# design.net
KiCad netlist of a schematic drawn in Altium Designer
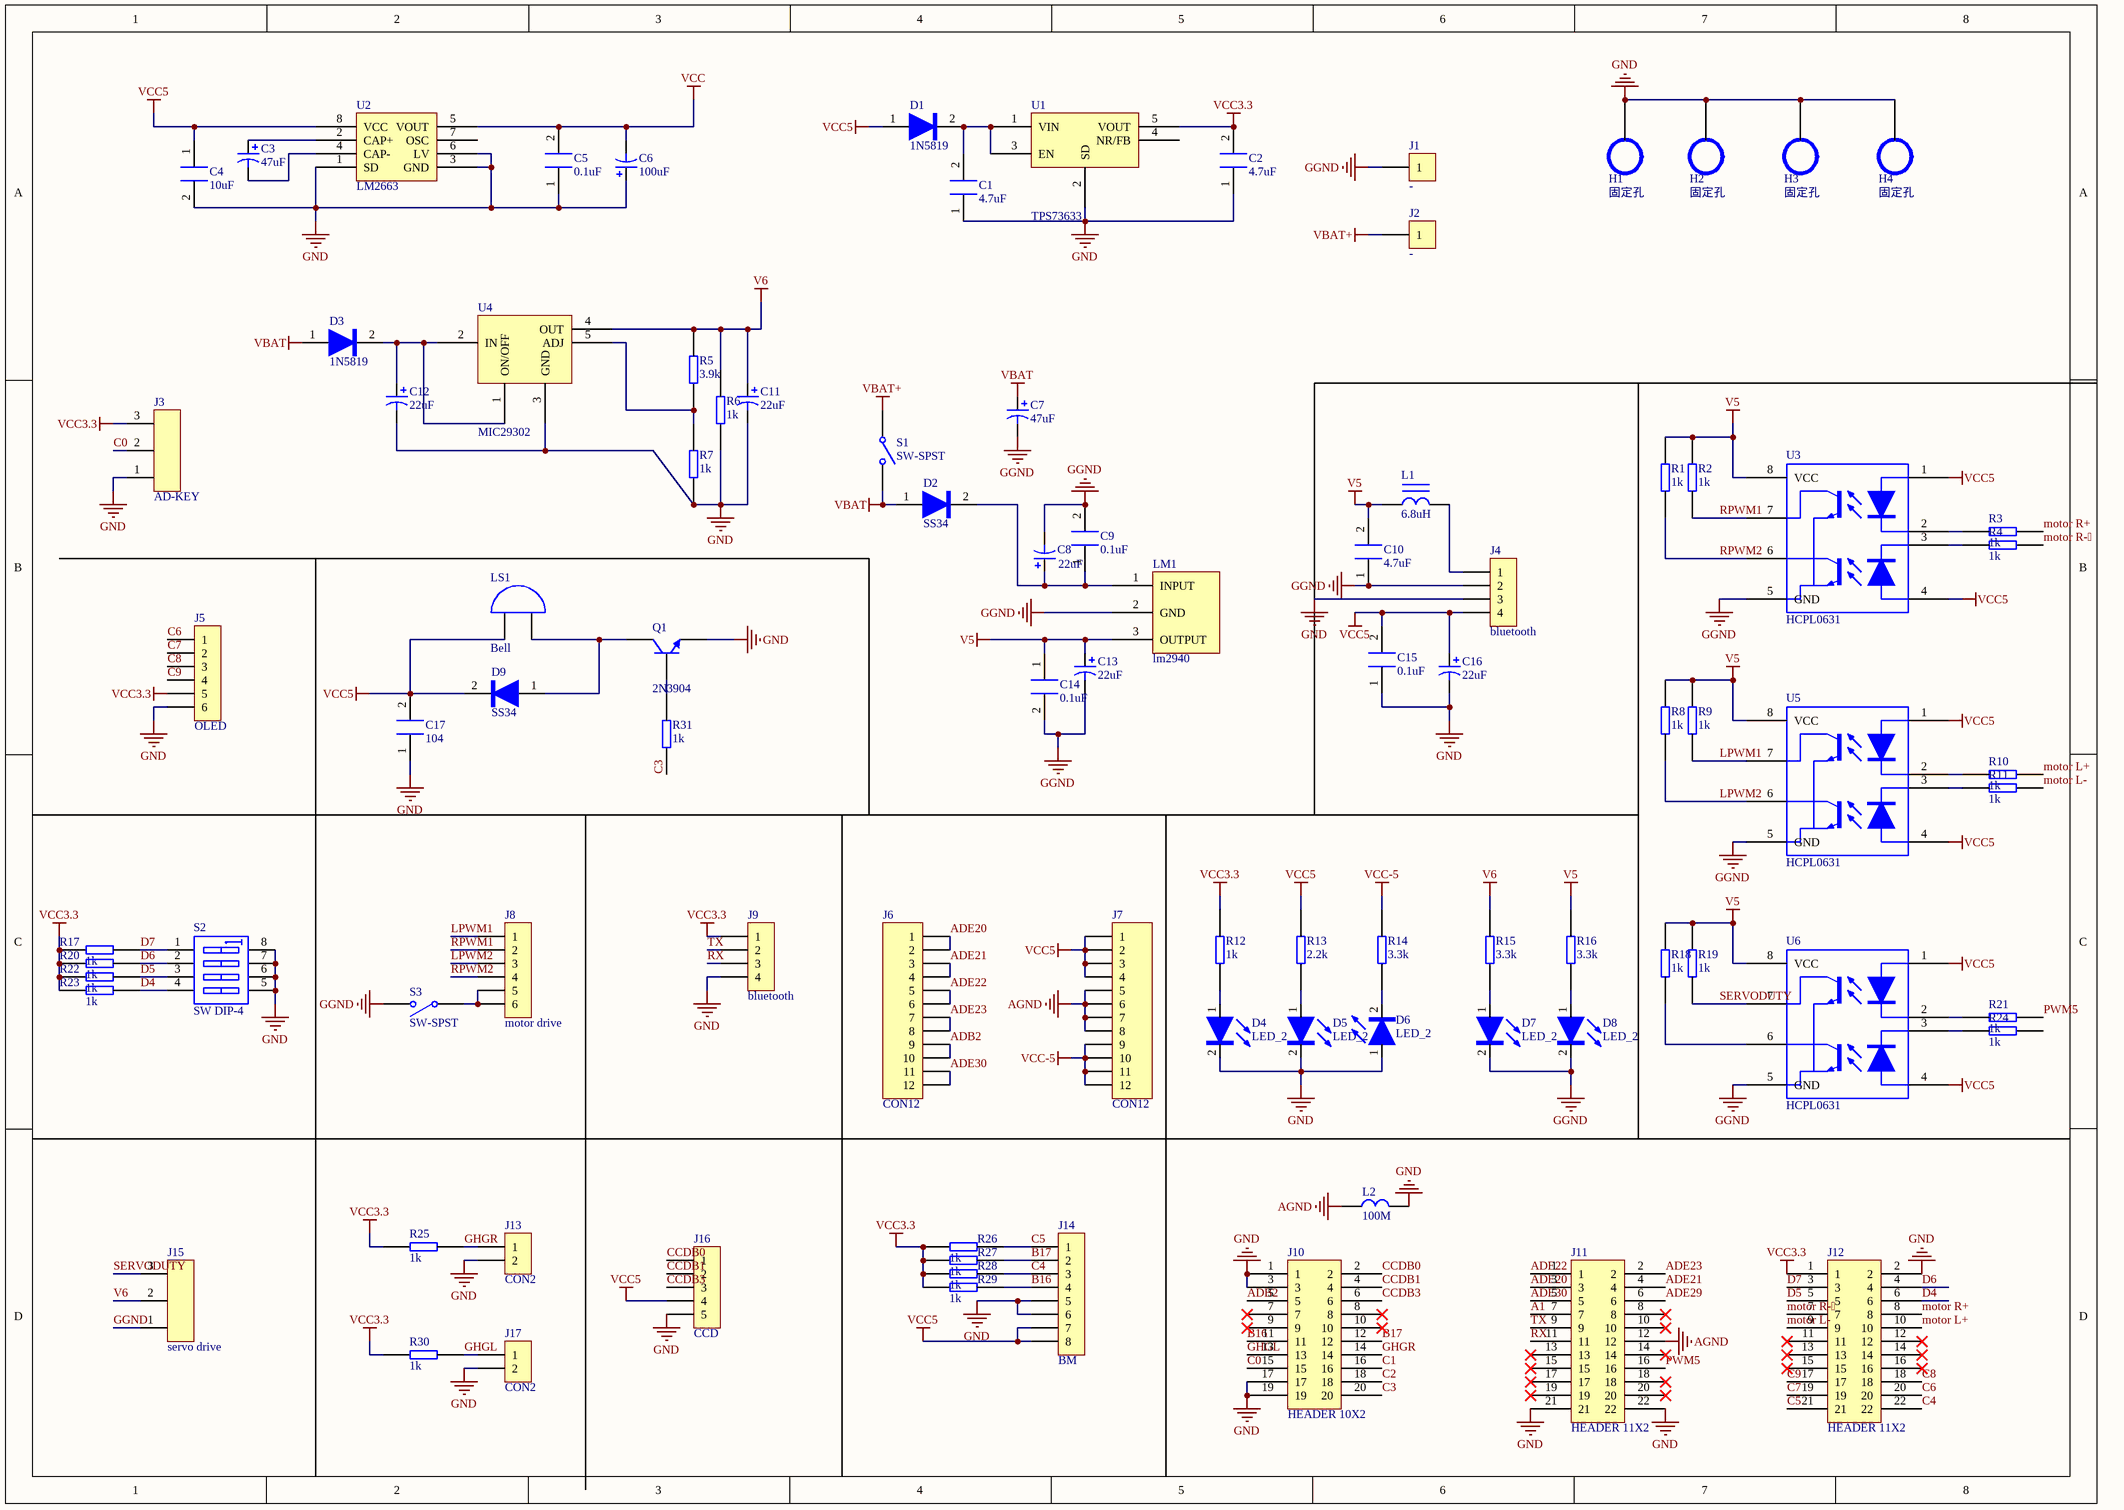
[diagram p0: 智能小车主板.SchDoc]

(export (version "E")
  (design (tool "Eeschema 10.0.6"))
  (components
    (comp (ref "C1")
      (value "4.7uF")
      (footprint "0805C")
      (description "电容")
      (libsource (lib "智能车主板") (part "CAP_2"))
    )
    (comp (ref "C2")
      (value "4.7uF")
      (footprint "0805C")
      (description "电容")
      (libsource (lib "智能车主板") (part "CAP_2"))
    )
    (comp (ref "C3")
      (value "47uF")
      (footprint "C型钽电容_6032_28")
      (description "极性电容")
      (libsource (lib "智能车主板") (part "极性电容"))
    )
    (comp (ref "C4")
      (value "10uF")
      (footprint "0805C")
      (description "电容")
      (libsource (lib "智能车主板") (part "CAP"))
    )
    (comp (ref "C5")
      (value "0.1uF")
      (footprint "0805C")
      (description "电容")
      (libsource (lib "智能车主板") (part "CAP_1"))
    )
    (comp (ref "C6")
      (value "100uF")
      (footprint "D型钽电容_7343_31")
      (description "极性电容")
      (libsource (lib "智能车主板") (part "极性电容_1"))
    )
    (comp (ref "C7")
      (value "47uF")
      (footprint "D型钽电容_7343_31")
      (description "极性电容")
      (libsource (lib "智能车主板") (part "极性电容"))
    )
    (comp (ref "C8")
      (value "22uF")
      (footprint "C型钽电容_6032_28")
      (description "极性电容")
      (libsource (lib "智能车主板") (part "极性电容_2"))
    )
    (comp (ref "C9")
      (value "0.1uF")
      (footprint "0805C")
      (description "电容")
      (libsource (lib "智能车主板") (part "CAP_1"))
    )
    (comp (ref "C10")
      (value "4.7uF")
      (footprint "0805C")
      (description "电容")
      (libsource (lib "智能车主板") (part "CAP_2"))
    )
    (comp (ref "C11")
      (value "22uF")
      (footprint "B型钽电容_3528_21")
      (description "极性电容")
      (libsource (lib "智能车主板") (part "极性电容_2"))
    )
    (comp (ref "C12")
      (value "22uF")
      (footprint "B型钽电容_3528_21")
      (description "极性电容")
      (libsource (lib "智能车主板") (part "极性电容_2"))
    )
    (comp (ref "C13")
      (value "22uF")
      (footprint "B型钽电容_3528_21")
      (description "极性电容")
      (libsource (lib "智能车主板") (part "极性电容_2"))
    )
    (comp (ref "C14")
      (value "0.1uF")
      (footprint "0805C")
      (description "电容")
      (libsource (lib "智能车主板") (part "CAP_1"))
    )
    (comp (ref "C15")
      (value "0.1uF")
      (footprint "0805C")
      (description "电容")
      (libsource (lib "智能车主板") (part "CAP_1"))
    )
    (comp (ref "C16")
      (value "22uF")
      (footprint "B型钽电容_3528_21")
      (description "极性电容")
      (libsource (lib "智能车主板") (part "极性电容_2"))
    )
    (comp (ref "C17")
      (value "104")
      (footprint "0805C")
      (description "电容")
      (libsource (lib "智能车主板") (part "CAP_3"))
    )
    (comp (ref "D1")
      (value "1N5819")
      (footprint "0805D")
      (description "二极管")
      (libsource (lib "智能车主板") (part "SS34"))
    )
    (comp (ref "D2")
      (value "SS34")
      (footprint "0805D")
      (description "二极管")
      (libsource (lib "智能车主板") (part "SS34_1"))
    )
    (comp (ref "D3")
      (value "1N5819")
      (footprint "0805D")
      (description "二极管")
      (libsource (lib "智能车主板") (part "SS34"))
    )
    (comp (ref "D4") (value "LED_2") (footprint "0805D") (libsource (lib "智能车主板") (part "LED")))
    (comp (ref "D5") (value "LED_2") (footprint "0805D") (libsource (lib "智能车主板") (part "LED")))
    (comp (ref "D6") (value "LED_2") (footprint "0805D") (libsource (lib "智能车主板") (part "LED")))
    (comp (ref "D7") (value "LED_2") (footprint "0805D") (libsource (lib "智能车主板") (part "LED")))
    (comp (ref "D8") (value "LED_2") (footprint "0805D") (libsource (lib "智能车主板") (part "LED")))
    (comp (ref "D9")
      (value "SS34")
      (footprint "SS34_3D")
      (description "二极管")
      (libsource (lib "智能车主板") (part "SS34_1"))
    )
    (comp (ref "H1") (value "固定孔") (footprint "铜柱孔3") (libsource (lib "智能车主板") (part "固定孔")))
    (comp (ref "H2") (value "固定孔") (footprint "铜柱孔3") (libsource (lib "智能车主板") (part "固定孔")))
    (comp (ref "H3") (value "固定孔") (footprint "铜柱孔3") (libsource (lib "智能车主板") (part "固定孔")))
    (comp (ref "H4") (value "固定孔") (footprint "铜柱孔3") (libsource (lib "智能车主板") (part "固定孔")))
    (comp (ref "J1")
      (value "-")
      (footprint "单面焊盘2*3MM_1PIN")
      (description "Connector")
      (libsource (lib "智能车主板") (part "CON1"))
    )
    (comp (ref "J2")
      (value "-")
      (footprint "单面焊盘2*3MM_1PIN")
      (description "Connector")
      (libsource (lib "智能车主板") (part "CON1"))
    )
    (comp (ref "J3")
      (value "AD-KEY")
      (footprint "HDR1X3")
      (description "SOCKET")
      (libsource (lib "智能车主板") (part "CON3"))
    )
    (comp (ref "J4")
      (value "bluetooth")
      (footprint "B0505S-2W")
      (description "Connector")
      (libsource (lib "智能车主板") (part "CON4"))
    )
    (comp (ref "J5")
      (value "OLED")
      (footprint "HDR1X6")
      (description "Connector")
      (libsource (lib "智能车主板") (part "CON6"))
    )
    (comp (ref "J6")
      (value "CON12")
      (footprint "HDR2X6")
      (description "Connector")
      (libsource (lib "") (part "CON12_1"))
    )
    (comp (ref "J7")
      (value "CON12")
      (footprint "HDR2X6")
      (description "Connector")
      (libsource (lib "智能车主板") (part "CON12"))
    )
    (comp (ref "J8")
      (value "motor drive")
      (footprint "HDR2X3")
      (description "Connector")
      (libsource (lib "智能车主板") (part "CON6_1"))
    )
    (comp (ref "J9")
      (value "bluetooth")
      (footprint "HDR1X4")
      (description "Connector")
      (libsource (lib "智能车主板") (part "CON4"))
    )
    (comp (ref "J10")
      (value "HEADER 10X2")
      (footprint "HDR2X10")
      (description "排针")
      (libsource (lib "智能车主板") (part "HEADER 10X2"))
    )
    (comp (ref "J11")
      (value "HEADER 11X2")
      (footprint "HDR2X11")
      (description "排针")
      (libsource (lib "智能车主板") (part "HEADER 11X2"))
    )
    (comp (ref "J12")
      (value "HEADER 11X2")
      (footprint "HDR2X11")
      (description "排针")
      (libsource (lib "智能车主板") (part "HEADER 11X2"))
    )
    (comp (ref "J13")
      (value "CON2")
      (footprint "2PIN杜邦插座_1.27mm")
      (description "Connector")
      (libsource (lib "智能车主板") (part "CON2"))
    )
    (comp (ref "J14")
      (value "BM")
      (footprint "HDR2X4")
      (description "Connector")
      (libsource (lib "智能车主板") (part "CON8"))
    )
    (comp (ref "J15")
      (value "servo drive")
      (footprint "HDR1X3")
      (description "SOCKET")
      (libsource (lib "智能车主板") (part "CON3_1"))
    )
    (comp (ref "J16")
      (value "CCD")
      (footprint "HDR1X5")
      (description "Connector")
      (libsource (lib "智能车主板") (part "CON5"))
    )
    (comp (ref "J17")
      (value "CON2")
      (footprint "2PIN杜邦插座_1.27mm")
      (description "Connector")
      (libsource (lib "智能车主板") (part "CON2"))
    )
    (comp (ref "L1")
      (value "6.8uH")
      (footprint "CDRH3D16_4.2*1.8")
      (description "电感")
      (libsource (lib "智能车主板") (part "INDUCTOR"))
    )
    (comp (ref "L2") (value "100M") (footprint "0603L") (libsource (lib "智能车主板") (part "INDUCTOR_2")))
    (comp (ref "LM1")
      (value "lm2940")
      (footprint "lm2940")
      (description "IC")
      (libsource (lib "智能车主板") (part "lm2940"))
    )
    (comp (ref "LS1")
      (value "Bell")
      (footprint "蜂鸣器侧装")
      (description "Electrical Bell")
      (fields (field (name "PUBLISHER") "Altium Limited"))
      (libsource (lib "智能车主板") (part "Bell"))
    )
    (comp (ref "Q1")
      (value "2N3904")
      (footprint "TO-92A")
      (description "NPN General Purpose Amplifier")
      (fields (field (name "PUBLISHER") "Altium Limited"))
      (libsource (lib "智能车主板") (part "2N3904"))
    )
    (comp (ref "R1")
      (value "1k")
      (footprint "0805R")
      (description "电阻")
      (libsource (lib "智能车主板") (part "RES_1"))
    )
    (comp (ref "R2")
      (value "1k")
      (footprint "0805R")
      (description "电阻")
      (libsource (lib "智能车主板") (part "RES_1"))
    )
    (comp (ref "R3")
      (value "1k")
      (footprint "0805R")
      (description "电阻")
      (libsource (lib "智能车主板") (part "RES_1"))
    )
    (comp (ref "R4")
      (value "1k")
      (footprint "0805R")
      (description "电阻")
      (libsource (lib "智能车主板") (part "RES_1"))
    )
    (comp (ref "R5")
      (value "3.9k")
      (footprint "0805R")
      (description "电阻")
      (libsource (lib "智能车主板") (part "RES"))
    )
    (comp (ref "R6")
      (value "1k")
      (footprint "0805R")
      (description "电阻")
      (libsource (lib "智能车主板") (part "RES_1"))
    )
    (comp (ref "R7")
      (value "1k")
      (footprint "0805R")
      (description "电阻")
      (libsource (lib "智能车主板") (part "RES_1"))
    )
    (comp (ref "R8")
      (value "1k")
      (footprint "0805R")
      (description "电阻")
      (libsource (lib "智能车主板") (part "RES_1"))
    )
    (comp (ref "R9")
      (value "1k")
      (footprint "0805R")
      (description "电阻")
      (libsource (lib "智能车主板") (part "RES_1"))
    )
    (comp (ref "R10")
      (value "1k")
      (footprint "0805R")
      (description "电阻")
      (libsource (lib "智能车主板") (part "RES_1"))
    )
    (comp (ref "R11")
      (value "1k")
      (footprint "0805R")
      (description "电阻")
      (libsource (lib "智能车主板") (part "RES_1"))
    )
    (comp (ref "R12")
      (value "1k")
      (footprint "0603R")
      (description "电阻")
      (libsource (lib "智能车主板") (part "RES_1"))
    )
    (comp (ref "R13")
      (value "2.2k")
      (footprint "0603R")
      (description "电阻")
      (libsource (lib "智能车主板") (part "RES_2"))
    )
    (comp (ref "R14")
      (value "3.3k")
      (footprint "0603R")
      (description "电阻")
      (libsource (lib "智能车主板") (part "RES_3"))
    )
    (comp (ref "R15")
      (value "3.3k")
      (footprint "0603R")
      (description "电阻")
      (libsource (lib "智能车主板") (part "RES_3"))
    )
    (comp (ref "R16")
      (value "3.3k")
      (footprint "0603R")
      (description "电阻")
      (libsource (lib "智能车主板") (part "RES_3"))
    )
    (comp (ref "R17")
      (value "1k")
      (footprint "0603R")
      (description "电阻")
      (libsource (lib "智能车主板") (part "RES_1"))
    )
    (comp (ref "R18")
      (value "1k")
      (footprint "0805R")
      (description "电阻")
      (libsource (lib "智能车主板") (part "RES_1"))
    )
    (comp (ref "R19")
      (value "1k")
      (footprint "0805R")
      (description "电阻")
      (libsource (lib "智能车主板") (part "RES_1"))
    )
    (comp (ref "R20")
      (value "1k")
      (footprint "0603R")
      (description "电阻")
      (libsource (lib "智能车主板") (part "RES_1"))
    )
    (comp (ref "R21")
      (value "1k")
      (footprint "0805R")
      (description "电阻")
      (libsource (lib "智能车主板") (part "RES_1"))
    )
    (comp (ref "R22")
      (value "1k")
      (footprint "0603R")
      (description "电阻")
      (libsource (lib "智能车主板") (part "RES_1"))
    )
    (comp (ref "R23")
      (value "1k")
      (footprint "0603R")
      (description "电阻")
      (libsource (lib "智能车主板") (part "RES_1"))
    )
    (comp (ref "R24")
      (value "1k")
      (footprint "0805R")
      (description "电阻")
      (libsource (lib "智能车主板") (part "RES_1"))
    )
    (comp (ref "R25")
      (value "1k")
      (footprint "0603R")
      (description "电阻")
      (libsource (lib "智能车主板") (part "RES_1"))
    )
    (comp (ref "R26")
      (value "1k")
      (footprint "0805R")
      (description "电阻")
      (libsource (lib "智能车主板") (part "RES_1"))
    )
    (comp (ref "R27")
      (value "1k")
      (footprint "0805R")
      (description "电阻")
      (libsource (lib "智能车主板") (part "RES_1"))
    )
    (comp (ref "R28")
      (value "1k")
      (footprint "0805R")
      (description "电阻")
      (libsource (lib "智能车主板") (part "RES_1"))
    )
    (comp (ref "R29")
      (value "1k")
      (footprint "0805R")
      (description "电阻")
      (libsource (lib "智能车主板") (part "RES_1"))
    )
    (comp (ref "R30")
      (value "1k")
      (footprint "0603R")
      (description "电阻")
      (libsource (lib "智能车主板") (part "RES_1"))
    )
    (comp (ref "R31")
      (value "1k")
      (footprint "0805R")
      (description "电阻")
      (libsource (lib "智能车主板") (part "RES_1"))
    )
    (comp (ref "S1")
      (value "SW-SPST")
      (footprint "开关")
      (description "Single-Pole, Single-Throw Switch")
      (fields (field (name "PUBLISHER") "Altium Limited"))
      (libsource (lib "智能车主板") (part "SW-SPST"))
    )
    (comp (ref "S2")
      (value "SW DIP-4")
      (footprint "4路拨码开关")
      (description "DIP Switch")
      (libsource (lib "智能车主板") (part "SW DIP-4"))
    )
    (comp (ref "S3")
      (value "SW-SPST")
      (footprint "开关")
      (description "Single-Pole, Single-Throw Switch")
      (fields (field (name "PUBLISHER") "Altium Limited"))
      (libsource (lib "智能车主板") (part "SW-SPST"))
    )
    (comp (ref "U1")
      (value "TPS73633")
      (footprint "SOT23_5-LEADS")
      (description "IC")
      (libsource (lib "智能车主板") (part "TPS73633"))
    )
    (comp (ref "U2")
      (value "LM2663")
      (footprint "SOP_8(OPA)")
      (description "IC")
      (libsource (lib "智能车主板") (part "LM2663"))
    )
    (comp (ref "U3")
      (value "HCPL0631")
      (footprint "SOP_8(OPA)")
      (description "光耦")
      (libsource (lib "智能车主板") (part "HCPL0631"))
    )
    (comp (ref "U4")
      (value "MIC29302")
      (footprint "TO_263_5(10.5*8.4mm)")
      (description "IC")
      (libsource (lib "智能车主板") (part "MIC29302"))
    )
    (comp (ref "U5")
      (value "HCPL0631")
      (footprint "SOP_8(OPA)")
      (description "光耦")
      (libsource (lib "智能车主板") (part "HCPL0631"))
    )
    (comp (ref "U6")
      (value "HCPL0631")
      (footprint "SOP_8(OPA)")
      (description "光耦")
      (libsource (lib "智能车主板") (part "HCPL0631"))
    )
  )
  (nets
    (net (code "1") (name "/A1") (class "Default")
      (node (ref "J11") (pin "7") (pinfunction "7_7") (pintype "passive"))
    )
    (net (code "2") (name "/ADB2") (class "Default")
      (node (ref "J10") (pin "5") (pinfunction "5_5") (pintype "passive"))
      (node (ref "J6") (pin "10") (pinfunction "10_10") (pintype "passive"))
      (node (ref "J6") (pin "9") (pinfunction "9_9") (pintype "passive"))
    )
    (net (code "3") (name "/ADE20") (class "Default")
      (node (ref "J11") (pin "3") (pinfunction "3_3") (pintype "passive"))
      (node (ref "J6") (pin "1") (pinfunction "1_1") (pintype "passive"))
      (node (ref "J6") (pin "2") (pinfunction "2_2") (pintype "passive"))
    )
    (net (code "4") (name "/ADE21") (class "Default")
      (node (ref "J11") (pin "4") (pinfunction "4_4") (pintype "passive"))
      (node (ref "J6") (pin "3") (pinfunction "3_3") (pintype "passive"))
      (node (ref "J6") (pin "4") (pinfunction "4_4") (pintype "passive"))
    )
    (net (code "5") (name "/ADE22") (class "Default")
      (node (ref "J11") (pin "1") (pinfunction "1_1") (pintype "passive"))
      (node (ref "J6") (pin "5") (pinfunction "5_5") (pintype "passive"))
      (node (ref "J6") (pin "6") (pinfunction "6_6") (pintype "passive"))
    )
    (net (code "6") (name "/ADE23") (class "Default")
      (node (ref "J11") (pin "2") (pinfunction "2_2") (pintype "passive"))
      (node (ref "J6") (pin "7") (pinfunction "7_7") (pintype "passive"))
      (node (ref "J6") (pin "8") (pinfunction "8_8") (pintype "passive"))
    )
    (net (code "7") (name "/ADE29") (class "Default")
      (node (ref "J11") (pin "6") (pinfunction "6_6") (pintype "passive"))
    )
    (net (code "8") (name "/ADE30") (class "Default")
      (node (ref "J11") (pin "5") (pinfunction "5_5") (pintype "passive"))
      (node (ref "J6") (pin "11") (pinfunction "11_11") (pintype "passive"))
      (node (ref "J6") (pin "12") (pinfunction "12_12") (pintype "passive"))
    )
    (net (code "9") (name "/B16") (class "Default")
      (node (ref "J10") (pin "11") (pinfunction "11_11") (pintype "passive"))
      (node (ref "J14") (pin "4") (pinfunction "4_4") (pintype "passive"))
      (node (ref "R29") (pin "2") (pinfunction "2_2") (pintype "passive"))
    )
    (net (code "10") (name "/B17") (class "Default")
      (node (ref "J10") (pin "12") (pinfunction "12_12") (pintype "passive"))
      (node (ref "J14") (pin "2") (pinfunction "2_2") (pintype "passive"))
      (node (ref "R27") (pin "2") (pinfunction "2_2") (pintype "passive"))
    )
    (net (code "11") (name "/C0") (class "Default")
      (node (ref "J10") (pin "15") (pinfunction "15_15") (pintype "passive"))
      (node (ref "J3") (pin "2") (pinfunction "2_2") (pintype "passive"))
    )
    (net (code "12") (name "/C1") (class "Default")
      (node (ref "J10") (pin "16") (pinfunction "16_16") (pintype "passive"))
    )
    (net (code "13") (name "/C2") (class "Default")
      (node (ref "J10") (pin "18") (pinfunction "18_18") (pintype "passive"))
    )
    (net (code "14") (name "/C3") (class "Default")
      (node (ref "J10") (pin "20") (pinfunction "20_20") (pintype "passive"))
      (node (ref "R31") (pin "1") (pinfunction "1_1") (pintype "passive"))
    )
    (net (code "15") (name "/C4") (class "Default")
      (node (ref "J12") (pin "22") (pinfunction "22_22") (pintype "passive"))
      (node (ref "J14") (pin "3") (pinfunction "3_3") (pintype "passive"))
      (node (ref "R28") (pin "2") (pinfunction "2_2") (pintype "passive"))
    )
    (net (code "16") (name "/C5") (class "Default")
      (node (ref "J12") (pin "21") (pinfunction "21_21") (pintype "passive"))
      (node (ref "J14") (pin "1") (pinfunction "1_1") (pintype "passive"))
      (node (ref "R26") (pin "2") (pinfunction "2_2") (pintype "passive"))
    )
    (net (code "17") (name "/C6") (class "Default")
      (node (ref "J12") (pin "20") (pinfunction "20_20") (pintype "passive"))
      (node (ref "J5") (pin "1") (pinfunction "1_1") (pintype "passive"))
    )
    (net (code "18") (name "/C7") (class "Default")
      (node (ref "J12") (pin "19") (pinfunction "19_19") (pintype "passive"))
      (node (ref "J5") (pin "2") (pinfunction "2_2") (pintype "passive"))
    )
    (net (code "19") (name "/C8") (class "Default")
      (node (ref "J12") (pin "18") (pinfunction "18_18") (pintype "passive"))
      (node (ref "J5") (pin "3") (pinfunction "3_3") (pintype "passive"))
    )
    (net (code "20") (name "/C9") (class "Default")
      (node (ref "J12") (pin "17") (pinfunction "17_17") (pintype "passive"))
      (node (ref "J5") (pin "4") (pinfunction "4_4") (pintype "passive"))
    )
    (net (code "21") (name "/CCDB0") (class "Default")
      (node (ref "J10") (pin "2") (pinfunction "2_2") (pintype "passive"))
      (node (ref "J16") (pin "1") (pinfunction "1_1") (pintype "passive"))
    )
    (net (code "22") (name "/CCDB1") (class "Default")
      (node (ref "J10") (pin "4") (pinfunction "4_4") (pintype "passive"))
      (node (ref "J16") (pin "2") (pinfunction "2_2") (pintype "passive"))
    )
    (net (code "23") (name "/CCDB3") (class "Default")
      (node (ref "J10") (pin "6") (pinfunction "6_6") (pintype "passive"))
      (node (ref "J16") (pin "3") (pinfunction "3_3") (pintype "passive"))
    )
    (net (code "24") (name "/D4") (class "Default")
      (node (ref "J12") (pin "6") (pinfunction "6_6") (pintype "passive"))
      (node (ref "R23") (pin "2") (pinfunction "2_2") (pintype "passive"))
      (node (ref "S2") (pin "4") (pinfunction "A4_4") (pintype "passive"))
    )
    (net (code "25") (name "/D5") (class "Default")
      (node (ref "J12") (pin "5") (pinfunction "5_5") (pintype "passive"))
      (node (ref "R22") (pin "2") (pinfunction "2_2") (pintype "passive"))
      (node (ref "S2") (pin "3") (pinfunction "A3_3") (pintype "passive"))
    )
    (net (code "26") (name "/D6") (class "Default")
      (node (ref "J12") (pin "4") (pinfunction "4_4") (pintype "passive"))
      (node (ref "R20") (pin "2") (pinfunction "2_2") (pintype "passive"))
      (node (ref "S2") (pin "2") (pinfunction "A2_2") (pintype "passive"))
    )
    (net (code "27") (name "/D7") (class "Default")
      (node (ref "J12") (pin "3") (pinfunction "3_3") (pintype "passive"))
      (node (ref "R17") (pin "2") (pinfunction "2_2") (pintype "passive"))
      (node (ref "S2") (pin "1") (pinfunction "A1_1") (pintype "passive"))
    )
    (net (code "28") (name "/GHGL") (class "Default")
      (node (ref "J10") (pin "13") (pinfunction "13_13") (pintype "passive"))
      (node (ref "J17") (pin "1") (pinfunction "1_1") (pintype "passive"))
      (node (ref "R30") (pin "2") (pinfunction "2_2") (pintype "passive"))
    )
    (net (code "29") (name "/GHGR") (class "Default")
      (node (ref "J10") (pin "14") (pinfunction "14_14") (pintype "passive"))
      (node (ref "J13") (pin "1") (pinfunction "1_1") (pintype "passive"))
      (node (ref "R25") (pin "2") (pinfunction "2_2") (pintype "passive"))
    )
    (net (code "30") (name "/LPWM1") (class "Default")
      (node (ref "J8") (pin "1") (pinfunction "1_1") (pintype "passive"))
      (node (ref "R9") (pin "2") (pinfunction "2_2") (pintype "passive"))
      (node (ref "U5") (pin "7") (pinfunction "7_7") (pintype "passive"))
    )
    (net (code "31") (name "/LPWM2") (class "Default")
      (node (ref "J8") (pin "3") (pinfunction "3_3") (pintype "passive"))
      (node (ref "R8") (pin "2") (pinfunction "2_2") (pintype "passive"))
      (node (ref "U5") (pin "6") (pinfunction "6_6") (pintype "passive"))
    )
    (net (code "32") (name "/PWM5") (class "Default")
      (node (ref "J11") (pin "16") (pinfunction "16_16") (pintype "passive"))
      (node (ref "R21") (pin "1") (pinfunction "1_1") (pintype "passive"))
    )
    (net (code "33") (name "/RPWM1") (class "Default")
      (node (ref "J8") (pin "2") (pinfunction "2_2") (pintype "passive"))
      (node (ref "R2") (pin "2") (pinfunction "2_2") (pintype "passive"))
      (node (ref "U3") (pin "7") (pinfunction "7_7") (pintype "passive"))
    )
    (net (code "34") (name "/RPWM2") (class "Default")
      (node (ref "J8") (pin "4") (pinfunction "4_4") (pintype "passive"))
      (node (ref "R1") (pin "2") (pinfunction "2_2") (pintype "passive"))
      (node (ref "U3") (pin "6") (pinfunction "6_6") (pintype "passive"))
    )
    (net (code "35") (name "/RX") (class "Default")
      (node (ref "J11") (pin "11") (pinfunction "11_11") (pintype "passive"))
      (node (ref "J9") (pin "3") (pinfunction "3_3") (pintype "passive"))
    )
    (net (code "36") (name "/SERVODUTY") (class "Default")
      (node (ref "J15") (pin "3") (pinfunction "3_3") (pintype "passive"))
      (node (ref "R19") (pin "2") (pinfunction "2_2") (pintype "passive"))
      (node (ref "U6") (pin "7") (pinfunction "7_7") (pintype "passive"))
    )
    (net (code "37") (name "/TX") (class "Default")
      (node (ref "J11") (pin "9") (pinfunction "9_9") (pintype "passive"))
      (node (ref "J9") (pin "2") (pinfunction "2_2") (pintype "passive"))
    )
    (net (code "38") (name "/motor L+") (class "Default")
      (node (ref "J12") (pin "10") (pinfunction "10_10") (pintype "passive"))
      (node (ref "R10") (pin "1") (pinfunction "1_1") (pintype "passive"))
    )
    (net (code "39") (name "/motor L-") (class "Default")
      (node (ref "J12") (pin "9") (pinfunction "9_9") (pintype "passive"))
      (node (ref "R11") (pin "1") (pinfunction "1_1") (pintype "passive"))
    )
    (net (code "40") (name "/motor R+") (class "Default")
      (node (ref "J12") (pin "8") (pinfunction "8_8") (pintype "passive"))
      (node (ref "R3") (pin "1") (pinfunction "1_1") (pintype "passive"))
    )
    (net (code "41") (name "/motor R-") (class "Default")
      (node (ref "J12") (pin "7") (pinfunction "7_7") (pintype "passive"))
      (node (ref "R4") (pin "1") (pinfunction "1_1") (pintype "passive"))
    )
    (net (code "42") (name "AGND") (class "Default")
      (node (ref "J11") (pin "12") (pinfunction "12_12") (pintype "passive"))
      (node (ref "J7") (pin "5") (pinfunction "5_5") (pintype "passive"))
      (node (ref "J7") (pin "6") (pinfunction "6_6") (pintype "passive"))
      (node (ref "J7") (pin "7") (pinfunction "7_7") (pintype "passive"))
      (node (ref "J7") (pin "8") (pinfunction "8_8") (pintype "passive"))
      (node (ref "L2") (pin "1") (pinfunction "1_1") (pintype "passive"))
    )
    (net (code "43") (name "GGND") (class "Default")
      (node (ref "C10") (pin "1") (pinfunction "1_1") (pintype "passive"))
      (node (ref "C13") (pin "2") (pinfunction "2_2") (pintype "passive"))
      (node (ref "C14") (pin "2") (pinfunction "2_2") (pintype "passive"))
      (node (ref "C7") (pin "2") (pinfunction "2_2") (pintype "passive"))
      (node (ref "C8") (pin "2") (pinfunction "2_2") (pintype "passive"))
      (node (ref "C9") (pin "2") (pinfunction "2_2") (pintype "passive"))
      (node (ref "D7") (pin "2") (pinfunction "2_2") (pintype "passive"))
      (node (ref "D8") (pin "2") (pinfunction "2_2") (pintype "passive"))
      (node (ref "J1") (pin "1") (pinfunction "1_1") (pintype "passive"))
      (node (ref "J15") (pin "1") (pinfunction "1_1") (pintype "passive"))
      (node (ref "J4") (pin "2") (pinfunction "2_2") (pintype "passive"))
      (node (ref "LM1") (pin "2") (pinfunction "GND_2") (pintype "passive"))
      (node (ref "S3") (pin "2") (pinfunction "NO_2") (pintype "passive"))
      (node (ref "U3") (pin "5") (pinfunction "GND_5") (pintype "passive"))
      (node (ref "U5") (pin "5") (pinfunction "GND_5") (pintype "passive"))
      (node (ref "U6") (pin "5") (pinfunction "GND_5") (pintype "passive"))
    )
    (net (code "44") (name "GND") (class "Default")
      (node (ref "C1") (pin "1") (pinfunction "1_1") (pintype "passive"))
      (node (ref "C11") (pin "2") (pinfunction "2_2") (pintype "passive"))
      (node (ref "C12") (pin "2") (pinfunction "2_2") (pintype "passive"))
      (node (ref "C15") (pin "1") (pinfunction "1_1") (pintype "passive"))
      (node (ref "C16") (pin "2") (pinfunction "2_2") (pintype "passive"))
      (node (ref "C17") (pin "1") (pinfunction "1_1") (pintype "passive"))
      (node (ref "C2") (pin "1") (pinfunction "1_1") (pintype "passive"))
      (node (ref "C4") (pin "2") (pinfunction "2_2") (pintype "passive"))
      (node (ref "C5") (pin "1") (pinfunction "1_1") (pintype "passive"))
      (node (ref "C6") (pin "1") (pinfunction "1_1") (pintype "passive"))
      (node (ref "D4") (pin "2") (pinfunction "2_2") (pintype "passive"))
      (node (ref "D5") (pin "2") (pinfunction "2_2") (pintype "passive"))
      (node (ref "D6") (pin "1") (pinfunction "1_1") (pintype "passive"))
      (node (ref "H1") (pin "11") (pinfunction "11_11") (pintype "passive"))
      (node (ref "H2") (pin "11") (pinfunction "11_11") (pintype "passive"))
      (node (ref "H3") (pin "11") (pinfunction "11_11") (pintype "passive"))
      (node (ref "H4") (pin "11") (pinfunction "11_11") (pintype "passive"))
      (node (ref "J10") (pin "1") (pinfunction "1_1") (pintype "passive"))
      (node (ref "J10") (pin "17") (pinfunction "17_17") (pintype "passive"))
      (node (ref "J10") (pin "19") (pinfunction "19_19") (pintype "passive"))
      (node (ref "J10") (pin "3") (pinfunction "3_3") (pintype "passive"))
      (node (ref "J11") (pin "21") (pinfunction "21_21") (pintype "passive"))
      (node (ref "J11") (pin "22") (pinfunction "22_22") (pintype "passive"))
      (node (ref "J12") (pin "2") (pinfunction "2_2") (pintype "passive"))
      (node (ref "J13") (pin "2") (pinfunction "2_2") (pintype "passive"))
      (node (ref "J14") (pin "5") (pinfunction "5_5") (pintype "passive"))
      (node (ref "J14") (pin "6") (pinfunction "6_6") (pintype "passive"))
      (node (ref "J16") (pin "5") (pinfunction "5_5") (pintype "passive"))
      (node (ref "J17") (pin "2") (pinfunction "2_2") (pintype "passive"))
      (node (ref "J3") (pin "1") (pinfunction "1_1") (pintype "passive"))
      (node (ref "J4") (pin "3") (pinfunction "3_3") (pintype "passive"))
      (node (ref "J5") (pin "6") (pinfunction "6_6") (pintype "passive"))
      (node (ref "J9") (pin "4") (pinfunction "4_4") (pintype "passive"))
      (node (ref "L2") (pin "2") (pinfunction "2_2") (pintype "passive"))
      (node (ref "Q1") (pin "1") (pinfunction "E_1") (pintype "passive"))
      (node (ref "R6") (pin "1") (pinfunction "1_1") (pintype "passive"))
      (node (ref "R7") (pin "1") (pinfunction "1_1") (pintype "passive"))
      (node (ref "S2") (pin "5") (pinfunction "B4_5") (pintype "passive"))
      (node (ref "S2") (pin "6") (pinfunction "B3_6") (pintype "passive"))
      (node (ref "S2") (pin "7") (pinfunction "B2_7") (pintype "passive"))
      (node (ref "S2") (pin "8") (pinfunction "B1_8") (pintype "passive"))
      (node (ref "U1") (pin "2") (pinfunction "SD_2") (pintype "passive"))
      (node (ref "U2") (pin "1") (pinfunction "SD_1") (pintype "passive"))
      (node (ref "U2") (pin "3") (pinfunction "GND_3") (pintype "passive"))
      (node (ref "U2") (pin "6") (pinfunction "LV_6") (pintype "passive"))
      (node (ref "U4") (pin "3") (pinfunction "GND_3") (pintype "passive"))
    )
    (net (code "45") (name "Net-(D4-Pad1)") (class "Default")
      (node (ref "D4") (pin "1") (pinfunction "1_1") (pintype "passive"))
      (node (ref "R12") (pin "1") (pinfunction "1_1") (pintype "passive"))
    )
    (net (code "46") (name "Net-(D5-Pad1)") (class "Default")
      (node (ref "D5") (pin "1") (pinfunction "1_1") (pintype "passive"))
      (node (ref "R13") (pin "1") (pinfunction "1_1") (pintype "passive"))
    )
    (net (code "47") (name "Net-(D6-Pad2)") (class "Default")
      (node (ref "D6") (pin "2") (pinfunction "2_2") (pintype "passive"))
      (node (ref "R14") (pin "1") (pinfunction "1_1") (pintype "passive"))
    )
    (net (code "48") (name "Net-(D7-Pad1)") (class "Default")
      (node (ref "D7") (pin "1") (pinfunction "1_1") (pintype "passive"))
      (node (ref "R15") (pin "1") (pinfunction "1_1") (pintype "passive"))
    )
    (net (code "49") (name "Net-(D8-Pad1)") (class "Default")
      (node (ref "D8") (pin "1") (pinfunction "1_1") (pintype "passive"))
      (node (ref "R16") (pin "1") (pinfunction "1_1") (pintype "passive"))
    )
    (net (code "50") (name "Net-(J4-Pad1)") (class "Default")
      (node (ref "J4") (pin "1") (pinfunction "1_1") (pintype "passive"))
      (node (ref "L1") (pin "2") (pinfunction "2_2") (pintype "passive"))
    )
    (net (code "51") (name "Net-(LM1-INPUT)") (class "Default")
      (node (ref "C8") (pin "1") (pinfunction "1_1") (pintype "passive"))
      (node (ref "C9") (pin "1") (pinfunction "1_1") (pintype "passive"))
      (node (ref "D2") (pin "2") (pinfunction "2_2") (pintype "passive"))
      (node (ref "LM1") (pin "1") (pinfunction "INPUT_1") (pintype "passive"))
    )
    (net (code "52") (name "Net-(LS1-B)") (class "Default")
      (node (ref "D9") (pin "1") (pinfunction "1_1") (pintype "passive"))
      (node (ref "LS1") (pin "2") (pinfunction "B_2") (pintype "passive"))
      (node (ref "Q1") (pin "3") (pinfunction "C_3") (pintype "passive"))
    )
    (net (code "53") (name "Net-(Q1-B)") (class "Default")
      (node (ref "Q1") (pin "2") (pinfunction "B_2") (pintype "passive"))
      (node (ref "R31") (pin "2") (pinfunction "2_2") (pintype "passive"))
    )
    (net (code "54") (name "Net-(R3-Pad2)") (class "Default")
      (node (ref "R3") (pin "2") (pinfunction "2_2") (pintype "passive"))
      (node (ref "U3") (pin "2") (pinfunction "2_2") (pintype "passive"))
    )
    (net (code "55") (name "Net-(R4-Pad2)") (class "Default")
      (node (ref "R4") (pin "2") (pinfunction "2_2") (pintype "passive"))
      (node (ref "U3") (pin "3") (pinfunction "3_3") (pintype "passive"))
    )
    (net (code "56") (name "Net-(R10-Pad2)") (class "Default")
      (node (ref "R10") (pin "2") (pinfunction "2_2") (pintype "passive"))
      (node (ref "U5") (pin "2") (pinfunction "2_2") (pintype "passive"))
    )
    (net (code "57") (name "Net-(R11-Pad2)") (class "Default")
      (node (ref "R11") (pin "2") (pinfunction "2_2") (pintype "passive"))
      (node (ref "U5") (pin "3") (pinfunction "3_3") (pintype "passive"))
    )
    (net (code "58") (name "Net-(R18-Pad2)") (class "Default")
      (node (ref "R18") (pin "2") (pinfunction "2_2") (pintype "passive"))
      (node (ref "U6") (pin "6") (pinfunction "6_6") (pintype "passive"))
    )
    (net (code "59") (name "Net-(R21-Pad2)") (class "Default")
      (node (ref "R21") (pin "2") (pinfunction "2_2") (pintype "passive"))
      (node (ref "U6") (pin "2") (pinfunction "2_2") (pintype "passive"))
    )
    (net (code "60") (name "Net-(R24-Pad2)") (class "Default")
      (node (ref "R24") (pin "2") (pinfunction "2_2") (pintype "passive"))
      (node (ref "U6") (pin "3") (pinfunction "3_3") (pintype "passive"))
    )
    (net (code "61") (name "Net-(S3-COMMON)") (class "Default")
      (node (ref "J8") (pin "5") (pinfunction "5_5") (pintype "passive"))
      (node (ref "J8") (pin "6") (pinfunction "6_6") (pintype "passive"))
      (node (ref "S3") (pin "1") (pinfunction "COMMON_1") (pintype "passive"))
    )
    (net (code "62") (name "Net-(U1-EN)") (class "Default")
      (node (ref "C1") (pin "2") (pinfunction "2_2") (pintype "passive"))
      (node (ref "D1") (pin "2") (pinfunction "2_2") (pintype "passive"))
      (node (ref "U1") (pin "1") (pinfunction "VIN_1") (pintype "passive"))
      (node (ref "U1") (pin "3") (pinfunction "EN_3") (pintype "passive"))
    )
    (net (code "63") (name "Net-(U2-CAP+)") (class "Default")
      (node (ref "C3") (pin "1") (pinfunction "1_1") (pintype "passive"))
      (node (ref "U2") (pin "2") (pinfunction "CAP+_2") (pintype "passive"))
    )
    (net (code "64") (name "Net-(U2-CAP-)") (class "Default")
      (node (ref "C3") (pin "2") (pinfunction "2_2") (pintype "passive"))
      (node (ref "U2") (pin "4") (pinfunction "CAP-_4") (pintype "passive"))
    )
    (net (code "65") (name "Net-(U4-ADJ)") (class "Default")
      (node (ref "R5") (pin "1") (pinfunction "1_1") (pintype "passive"))
      (node (ref "R7") (pin "2") (pinfunction "2_2") (pintype "passive"))
      (node (ref "U4") (pin "5") (pinfunction "ADJ_5") (pintype "passive"))
    )
    (net (code "66") (name "Net-(U4-IN)") (class "Default")
      (node (ref "C12") (pin "1") (pinfunction "1_1") (pintype "passive"))
      (node (ref "D3") (pin "2") (pinfunction "2_2") (pintype "passive"))
      (node (ref "U4") (pin "1") (pinfunction "ON/OFF_1") (pintype "passive"))
      (node (ref "U4") (pin "2") (pinfunction "IN_2") (pintype "passive"))
    )
    (net (code "67") (name "V5") (class "Default")
      (node (ref "C10") (pin "2") (pinfunction "2_2") (pintype "passive"))
      (node (ref "C13") (pin "1") (pinfunction "1_1") (pintype "passive"))
      (node (ref "C14") (pin "1") (pinfunction "1_1") (pintype "passive"))
      (node (ref "L1") (pin "1") (pinfunction "1_1") (pintype "passive"))
      (node (ref "LM1") (pin "3") (pinfunction "OUTPUT_3") (pintype "passive"))
      (node (ref "R1") (pin "1") (pinfunction "1_1") (pintype "passive"))
      (node (ref "R16") (pin "2") (pinfunction "2_2") (pintype "passive"))
      (node (ref "R18") (pin "1") (pinfunction "1_1") (pintype "passive"))
      (node (ref "R19") (pin "1") (pinfunction "1_1") (pintype "passive"))
      (node (ref "R2") (pin "1") (pinfunction "1_1") (pintype "passive"))
      (node (ref "R8") (pin "1") (pinfunction "1_1") (pintype "passive"))
      (node (ref "R9") (pin "1") (pinfunction "1_1") (pintype "passive"))
      (node (ref "U3") (pin "8") (pinfunction "VCC_8") (pintype "passive"))
      (node (ref "U5") (pin "8") (pinfunction "VCC_8") (pintype "passive"))
      (node (ref "U6") (pin "8") (pinfunction "VCC_8") (pintype "passive"))
    )
    (net (code "68") (name "V6") (class "Default")
      (node (ref "C11") (pin "1") (pinfunction "1_1") (pintype "passive"))
      (node (ref "J15") (pin "2") (pinfunction "2_2") (pintype "passive"))
      (node (ref "R15") (pin "2") (pinfunction "2_2") (pintype "passive"))
      (node (ref "R5") (pin "2") (pinfunction "2_2") (pintype "passive"))
      (node (ref "R6") (pin "2") (pinfunction "2_2") (pintype "passive"))
      (node (ref "U4") (pin "4") (pinfunction "OUT_4") (pintype "passive"))
    )
    (net (code "69") (name "VBAT") (class "Default")
      (node (ref "C7") (pin "1") (pinfunction "1_1") (pintype "passive"))
      (node (ref "D2") (pin "1") (pinfunction "1_1") (pintype "passive"))
      (node (ref "D3") (pin "1") (pinfunction "1_1") (pintype "passive"))
      (node (ref "S1") (pin "2") (pinfunction "NO_2") (pintype "passive"))
    )
    (net (code "70") (name "VBAT+") (class "Default")
      (node (ref "J2") (pin "1") (pinfunction "1_1") (pintype "passive"))
      (node (ref "S1") (pin "1") (pinfunction "COMMON_1") (pintype "passive"))
    )
    (net (code "71") (name "VCC") (class "Default")
      (node (ref "C5") (pin "2") (pinfunction "2_2") (pintype "passive"))
      (node (ref "C6") (pin "2") (pinfunction "2_2") (pintype "passive"))
      (node (ref "U2") (pin "5") (pinfunction "VOUT_5") (pintype "passive"))
    )
    (net (code "72") (name "VCC-5") (class "Default")
      (node (ref "J7") (pin "10") (pinfunction "10_10") (pintype "passive"))
      (node (ref "J7") (pin "11") (pinfunction "11_11") (pintype "passive"))
      (node (ref "J7") (pin "12") (pinfunction "12_12") (pintype "passive"))
      (node (ref "J7") (pin "9") (pinfunction "9_9") (pintype "passive"))
      (node (ref "R14") (pin "2") (pinfunction "2_2") (pintype "passive"))
    )
    (net (code "73") (name "VCC3.3") (class "Default")
      (node (ref "C2") (pin "2") (pinfunction "2_2") (pintype "passive"))
      (node (ref "J12") (pin "1") (pinfunction "1_1") (pintype "passive"))
      (node (ref "J3") (pin "3") (pinfunction "3_3") (pintype "passive"))
      (node (ref "J5") (pin "5") (pinfunction "5_5") (pintype "passive"))
      (node (ref "J9") (pin "1") (pinfunction "1_1") (pintype "passive"))
      (node (ref "R12") (pin "2") (pinfunction "2_2") (pintype "passive"))
      (node (ref "R17") (pin "1") (pinfunction "1_1") (pintype "passive"))
      (node (ref "R20") (pin "1") (pinfunction "1_1") (pintype "passive"))
      (node (ref "R22") (pin "1") (pinfunction "1_1") (pintype "passive"))
      (node (ref "R23") (pin "1") (pinfunction "1_1") (pintype "passive"))
      (node (ref "R25") (pin "1") (pinfunction "1_1") (pintype "passive"))
      (node (ref "R26") (pin "1") (pinfunction "1_1") (pintype "passive"))
      (node (ref "R27") (pin "1") (pinfunction "1_1") (pintype "passive"))
      (node (ref "R28") (pin "1") (pinfunction "1_1") (pintype "passive"))
      (node (ref "R29") (pin "1") (pinfunction "1_1") (pintype "passive"))
      (node (ref "R30") (pin "1") (pinfunction "1_1") (pintype "passive"))
      (node (ref "U1") (pin "5") (pinfunction "VOUT_5") (pintype "passive"))
    )
    (net (code "74") (name "VCC5") (class "Default")
      (node (ref "C15") (pin "2") (pinfunction "2_2") (pintype "passive"))
      (node (ref "C16") (pin "1") (pinfunction "1_1") (pintype "passive"))
      (node (ref "C17") (pin "2") (pinfunction "2_2") (pintype "passive"))
      (node (ref "C4") (pin "1") (pinfunction "1_1") (pintype "passive"))
      (node (ref "D1") (pin "1") (pinfunction "1_1") (pintype "passive"))
      (node (ref "D9") (pin "2") (pinfunction "2_2") (pintype "passive"))
      (node (ref "J14") (pin "7") (pinfunction "7_7") (pintype "passive"))
      (node (ref "J14") (pin "8") (pinfunction "8_8") (pintype "passive"))
      (node (ref "J16") (pin "4") (pinfunction "4_4") (pintype "passive"))
      (node (ref "J4") (pin "4") (pinfunction "4_4") (pintype "passive"))
      (node (ref "J7") (pin "1") (pinfunction "1_1") (pintype "passive"))
      (node (ref "J7") (pin "2") (pinfunction "2_2") (pintype "passive"))
      (node (ref "J7") (pin "3") (pinfunction "3_3") (pintype "passive"))
      (node (ref "J7") (pin "4") (pinfunction "4_4") (pintype "passive"))
      (node (ref "LS1") (pin "1") (pinfunction "A_1") (pintype "passive"))
      (node (ref "R13") (pin "2") (pinfunction "2_2") (pintype "passive"))
      (node (ref "U2") (pin "8") (pinfunction "VCC_8") (pintype "passive"))
      (node (ref "U3") (pin "1") (pinfunction "1_1") (pintype "passive"))
      (node (ref "U3") (pin "4") (pinfunction "4_4") (pintype "passive"))
      (node (ref "U5") (pin "1") (pinfunction "1_1") (pintype "passive"))
      (node (ref "U5") (pin "4") (pinfunction "4_4") (pintype "passive"))
      (node (ref "U6") (pin "1") (pinfunction "1_1") (pintype "passive"))
      (node (ref "U6") (pin "4") (pinfunction "4_4") (pintype "passive"))
    )
    (net (code "75") (name "unconnected-(J10-Pad7)") (class "Default")
      (node (ref "J10") (pin "7") (pinfunction "7_7") (pintype "passive+no_connect"))
    )
    (net (code "76") (name "unconnected-(J10-Pad8)") (class "Default")
      (node (ref "J10") (pin "8") (pinfunction "8_8") (pintype "passive+no_connect"))
    )
    (net (code "77") (name "unconnected-(J10-Pad9)") (class "Default")
      (node (ref "J10") (pin "9") (pinfunction "9_9") (pintype "passive+no_connect"))
    )
    (net (code "78") (name "unconnected-(J10-Pad10)") (class "Default")
      (node (ref "J10") (pin "10") (pinfunction "10_10") (pintype "passive+no_connect"))
    )
    (net (code "79") (name "unconnected-(J11-Pad8)") (class "Default")
      (node (ref "J11") (pin "8") (pinfunction "8_8") (pintype "passive+no_connect"))
    )
    (net (code "80") (name "unconnected-(J11-Pad10)") (class "Default")
      (node (ref "J11") (pin "10") (pinfunction "10_10") (pintype "passive+no_connect"))
    )
    (net (code "81") (name "unconnected-(J11-Pad13)") (class "Default")
      (node (ref "J11") (pin "13") (pinfunction "13_13") (pintype "passive+no_connect"))
    )
    (net (code "82") (name "unconnected-(J11-Pad14)") (class "Default")
      (node (ref "J11") (pin "14") (pinfunction "14_14") (pintype "passive+no_connect"))
    )
    (net (code "83") (name "unconnected-(J11-Pad15)") (class "Default")
      (node (ref "J11") (pin "15") (pinfunction "15_15") (pintype "passive+no_connect"))
    )
    (net (code "84") (name "unconnected-(J11-Pad17)") (class "Default")
      (node (ref "J11") (pin "17") (pinfunction "17_17") (pintype "passive+no_connect"))
    )
    (net (code "85") (name "unconnected-(J11-Pad18)") (class "Default")
      (node (ref "J11") (pin "18") (pinfunction "18_18") (pintype "passive+no_connect"))
    )
    (net (code "86") (name "unconnected-(J11-Pad19)") (class "Default")
      (node (ref "J11") (pin "19") (pinfunction "19_19") (pintype "passive+no_connect"))
    )
    (net (code "87") (name "unconnected-(J11-Pad20)") (class "Default")
      (node (ref "J11") (pin "20") (pinfunction "20_20") (pintype "passive+no_connect"))
    )
    (net (code "88") (name "unconnected-(J12-Pad11)") (class "Default")
      (node (ref "J12") (pin "11") (pinfunction "11_11") (pintype "passive+no_connect"))
    )
    (net (code "89") (name "unconnected-(J12-Pad12)") (class "Default")
      (node (ref "J12") (pin "12") (pinfunction "12_12") (pintype "passive+no_connect"))
    )
    (net (code "90") (name "unconnected-(J12-Pad13)") (class "Default")
      (node (ref "J12") (pin "13") (pinfunction "13_13") (pintype "passive+no_connect"))
    )
    (net (code "91") (name "unconnected-(J12-Pad14)") (class "Default")
      (node (ref "J12") (pin "14") (pinfunction "14_14") (pintype "passive+no_connect"))
    )
    (net (code "92") (name "unconnected-(J12-Pad15)") (class "Default")
      (node (ref "J12") (pin "15") (pinfunction "15_15") (pintype "passive+no_connect"))
    )
    (net (code "93") (name "unconnected-(J12-Pad16)") (class "Default")
      (node (ref "J12") (pin "16") (pinfunction "16_16") (pintype "passive+no_connect"))
    )
    (net (code "94") (name "unconnected-(R24-Pad1)") (class "Default")
      (node (ref "R24") (pin "1") (pinfunction "1_1") (pintype "passive"))
    )
    (net (code "95") (name "unconnected-(U1-NR{slash}FB-Pad4)") (class "Default")
      (node (ref "U1") (pin "4") (pinfunction "NR/FB_4") (pintype "passive"))
    )
    (net (code "96") (name "unconnected-(U2-OSC-Pad7)") (class "Default")
      (node (ref "U2") (pin "7") (pinfunction "OSC_7") (pintype "passive"))
    )
  )
)
